# Power.net
KiCad netlist of a schematic drawn in Altium Designer
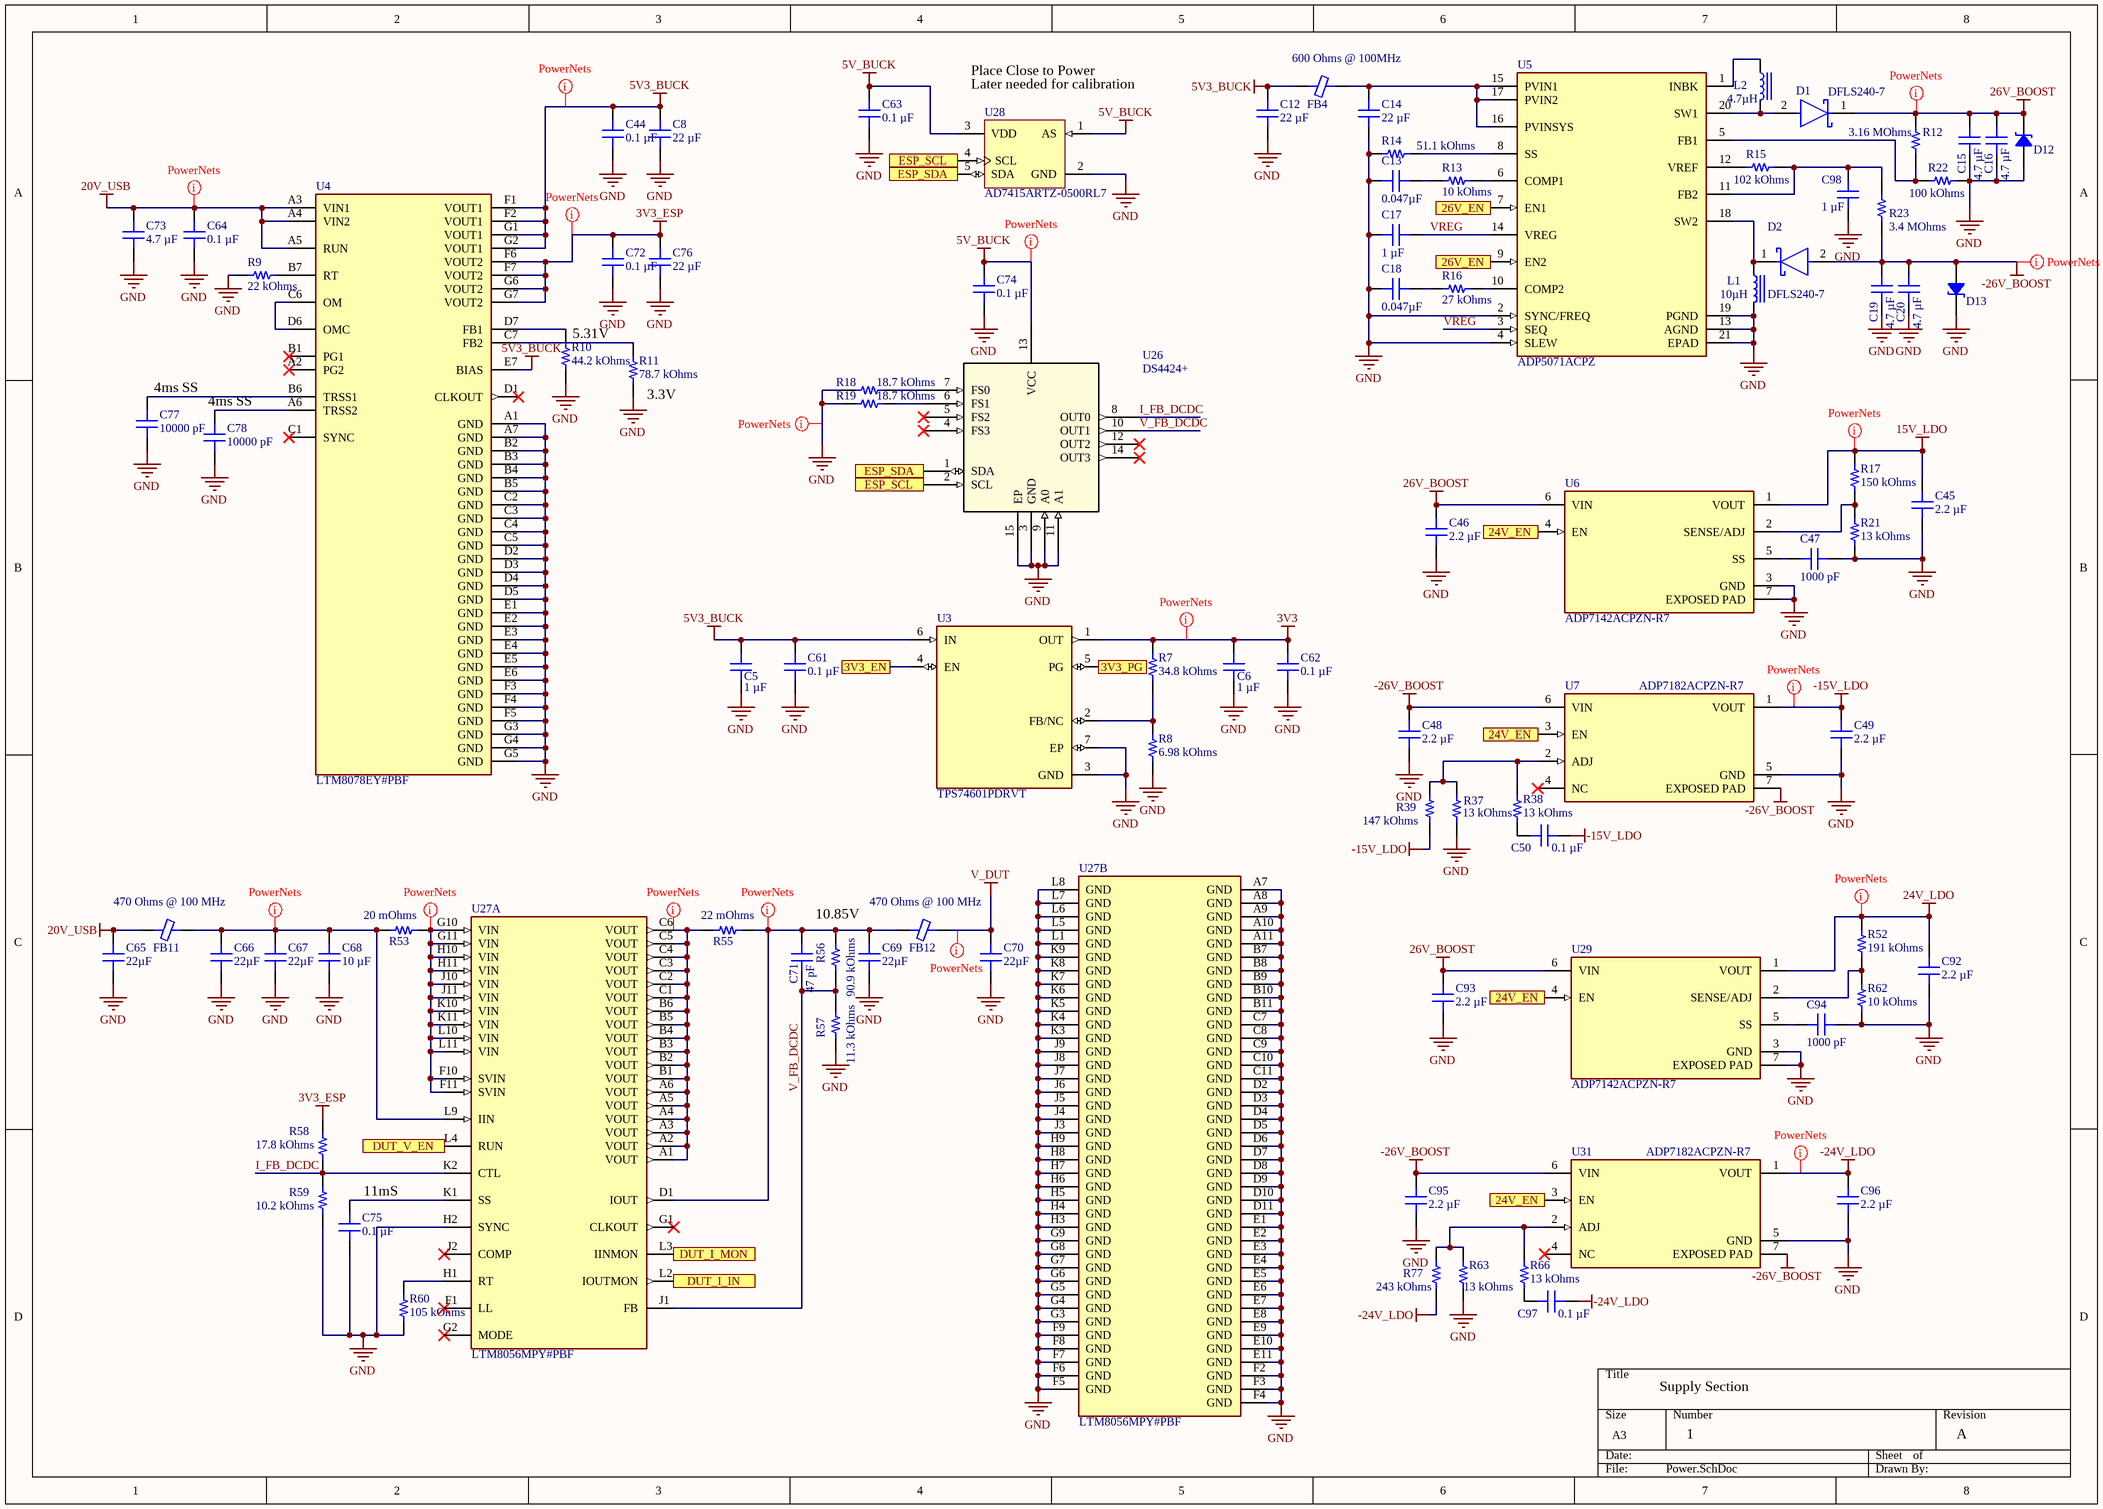
[diagram p0: Power.SchDoc]

(export (version "E")
  (design (tool "Eeschema 10.0.6"))
  (components
    (comp (ref "C5")
      (value "1 µF")
      (footprint "CAP 0603_1608")
      (description "SMT Capacitor")
      (fields
        (field (name "PART NUMBER") "GMC10X7R105M50NT")
        (field (name "MANUFACTURER") "Cal-Chip Electronics, Inc.")
      )
      (libsource (lib "Altium DB") (part "Capacitor"))
    )
    (comp (ref "C6")
      (value "1 µF")
      (footprint "CAP 0603_1608")
      (description "SMT Capacitor")
      (fields
        (field (name "PART NUMBER") "GMC10X7R105M50NT")
        (field (name "MANUFACTURER") "Cal-Chip Electronics, Inc.")
      )
      (libsource (lib "Altium DB") (part "Capacitor"))
    )
    (comp (ref "C8")
      (value "22 µF")
      (footprint "CAP 0603_1608")
      (description "SMT Capacitor")
      (fields
        (field (name "PART NUMBER") "GRM188C61C226ME01D")
        (field (name "MANUFACTURER") "Murata Electronics")
      )
      (libsource (lib "Altium DB") (part "Capacitor"))
    )
    (comp (ref "C12")
      (value "22 µF")
      (footprint "CAP 0603_1608")
      (description "SMT Capacitor")
      (fields
        (field (name "PART NUMBER") "GRM188C61C226ME01D")
        (field (name "MANUFACTURER") "Murata Electronics")
      )
      (libsource (lib "Altium DB") (part "Capacitor"))
    )
    (comp (ref "C13")
      (value "0.047µF")
      (footprint "CAP 0603_1608")
      (description "CAP CER 0.047UF 25V X7R 0603")
      (fields (field (name "MANUFACTURER") "KEMET") (field (name "PART NUMBER") "C0603C473K3RACAUTO"))
      (libsource (lib "") (part "Capacitor_4"))
    )
    (comp (ref "C14")
      (value "22 µF")
      (footprint "CAP 0603_1608")
      (description "SMT Capacitor")
      (fields
        (field (name "PART NUMBER") "GRM188C61C226ME01D")
        (field (name "MANUFACTURER") "Murata Electronics")
      )
      (libsource (lib "Altium DB") (part "Capacitor"))
    )
    (comp (ref "C15")
      (value "4.7 µF")
      (footprint "CAP 0805_2012")
      (description "CAP CER 4.7UF 50V X7R 0805")
      (fields
        (field (name "MANUFACTURER") "TDK Corporation")
        (field (name "PART NUMBER") "CGA4J1X7R1H475K125AC")
      )
      (libsource (lib "") (part "Capacitor_4"))
    )
    (comp (ref "C16")
      (value "4.7 µF")
      (footprint "CAP 0805_2012")
      (description "CAP CER 4.7UF 50V X7R 0805")
      (fields
        (field (name "MANUFACTURER") "TDK Corporation")
        (field (name "PART NUMBER") "CGA4J1X7R1H475K125AC")
      )
      (libsource (lib "") (part "Capacitor_4"))
    )
    (comp (ref "C17")
      (value "1 µF")
      (footprint "CAP 0603_1608")
      (description "SMT Capacitor")
      (fields
        (field (name "PART NUMBER") "GMC10X7R105M50NT")
        (field (name "MANUFACTURER") "Cal-Chip Electronics, Inc.")
      )
      (libsource (lib "Altium DB") (part "Capacitor"))
    )
    (comp (ref "C18")
      (value "0.047µF")
      (footprint "CAP 0603_1608")
      (description "CAP CER 0.047UF 25V X7R 0603")
      (fields (field (name "MANUFACTURER") "KEMET") (field (name "PART NUMBER") "C0603C473K3RACAUTO"))
      (libsource (lib "") (part "Capacitor_4"))
    )
    (comp (ref "C19")
      (value "4.7 µF")
      (footprint "CAP 0805_2012")
      (description "CAP CER 4.7UF 50V X7R 0805")
      (fields
        (field (name "MANUFACTURER") "TDK Corporation")
        (field (name "PART NUMBER") "CGA4J1X7R1H475K125AC")
      )
      (libsource (lib "") (part "Capacitor_4"))
    )
    (comp (ref "C20")
      (value "4.7 µF")
      (footprint "CAP 0805_2012")
      (description "CAP CER 4.7UF 50V X7R 0805")
      (fields
        (field (name "MANUFACTURER") "TDK Corporation")
        (field (name "PART NUMBER") "CGA4J1X7R1H475K125AC")
      )
      (libsource (lib "") (part "Capacitor_4"))
    )
    (comp (ref "C44")
      (value "0.1 µF")
      (footprint "CAP 0603_1608")
      (description "SMT Capacitor")
      (fields (field (name "PART NUMBER") "C0603C104M5RACTU") (field (name "MANUFACTURER") "KEMET"))
      (libsource (lib "Altium DB") (part "Capacitor"))
    )
    (comp (ref "C45")
      (value "2.2 µF")
      (footprint "CAP 0805_2012")
      (description "SMT Capacitor")
      (fields (field (name "PART NUMBER") "UMK212BB7225KG-T") (field (name "MANUFACTURER") "Taiyo Yuden"))
      (libsource (lib "Altium DB") (part "Capacitor"))
    )
    (comp (ref "C46")
      (value "2.2 µF")
      (footprint "CAP 0805_2012")
      (description "SMT Capacitor")
      (fields (field (name "PART NUMBER") "UMK212BB7225KG-T") (field (name "MANUFACTURER") "Taiyo Yuden"))
      (libsource (lib "Altium DB") (part "Capacitor"))
    )
    (comp (ref "C47")
      (value "1000 pF")
      (footprint "CAP 0603_1608")
      (description "CAP CER 1000PF 25V X7R 0603")
      (fields
        (field (name "MANUFACTURER") "Murata Electronics")
        (field (name "PART NUMBER") "GCJ188R71E102KA01D")
      )
      (libsource (lib "") (part "Capacitor_4"))
    )
    (comp (ref "C48")
      (value "2.2 µF")
      (footprint "CAP 0805_2012")
      (description "SMT Capacitor")
      (fields (field (name "PART NUMBER") "UMK212BB7225KG-T") (field (name "MANUFACTURER") "Taiyo Yuden"))
      (libsource (lib "Altium DB") (part "Capacitor"))
    )
    (comp (ref "C49")
      (value "2.2 µF")
      (footprint "CAP 0805_2012")
      (description "SMT Capacitor")
      (fields (field (name "PART NUMBER") "UMK212BB7225KG-T") (field (name "MANUFACTURER") "Taiyo Yuden"))
      (libsource (lib "Altium DB") (part "Capacitor"))
    )
    (comp (ref "C50")
      (value "0.1 µF")
      (footprint "CAP 0603_1608")
      (description "SMT Capacitor")
      (fields (field (name "PART NUMBER") "C0603C104M5RACTU") (field (name "MANUFACTURER") "KEMET"))
      (libsource (lib "Altium DB") (part "Capacitor"))
    )
    (comp (ref "C61")
      (value "0.1 µF")
      (footprint "CAP 0603_1608")
      (description "SMT Capacitor")
      (fields (field (name "PART NUMBER") "C0603C104M5RACTU") (field (name "MANUFACTURER") "KEMET"))
      (libsource (lib "Altium DB") (part "Capacitor"))
    )
    (comp (ref "C62")
      (value "0.1 µF")
      (footprint "CAP 0603_1608")
      (description "SMT Capacitor")
      (fields (field (name "PART NUMBER") "C0603C104M5RACTU") (field (name "MANUFACTURER") "KEMET"))
      (libsource (lib "Altium DB") (part "Capacitor"))
    )
    (comp (ref "C63")
      (value "0.1 µF")
      (footprint "CAP 0603_1608")
      (description "SMT Capacitor")
      (fields (field (name "PART NUMBER") "C0603C104M5RACTU") (field (name "MANUFACTURER") "KEMET"))
      (libsource (lib "Altium DB") (part "Capacitor"))
    )
    (comp (ref "C64")
      (value "0.1 µF")
      (footprint "CAP 0603_1608")
      (description "SMT Capacitor")
      (fields (field (name "PART NUMBER") "C0603C104M5RACTU") (field (name "MANUFACTURER") "KEMET"))
      (libsource (lib "Altium DB") (part "Capacitor"))
    )
    (comp (ref "C65")
      (value "22µF")
      (footprint "CAP 2220_5650 3.0MM")
      (description "CAP 2220 X7R 50V 22UF 20% 2.50MM")
      (fields
        (field (name "MANUFACTURER") "TDK Corporation")
        (field (name "PART NUMBER") "CGA9P3X7R1H226M250KB")
      )
      (libsource (lib "") (part "Capacitor_10"))
    )
    (comp (ref "C66")
      (value "22µF")
      (footprint "CAP 2220_5650 3.0MM")
      (description "CAP 2220 X7R 50V 22UF 20% 2.50MM")
      (fields
        (field (name "MANUFACTURER") "TDK Corporation")
        (field (name "PART NUMBER") "CGA9P3X7R1H226M250KB")
      )
      (libsource (lib "") (part "Capacitor_3"))
    )
    (comp (ref "C67")
      (value "22µF")
      (footprint "CAP 2220_5650 3.0MM")
      (description "CAP 2220 X7R 50V 22UF 20% 2.50MM")
      (fields
        (field (name "MANUFACTURER") "TDK Corporation")
        (field (name "PART NUMBER") "CGA9P3X7R1H226M250KB")
      )
      (libsource (lib "") (part "Capacitor_9"))
    )
    (comp (ref "C68")
      (value "10 µF")
      (footprint "CAP 1210_3225 - 1MM")
      (description "CAP CER 10UF 50V X7R 1210")
      (fields
        (field (name "MANUFACTURER") "Walsin Technology Corporation")
        (field (name "PART NUMBER") "1210B106K500CT")
      )
      (libsource (lib "") (part "Capacitor_5"))
    )
    (comp (ref "C69")
      (value "22µF")
      (footprint "CAP 2220_5650 3.0MM")
      (description "CAP 2220 X7R 50V 22UF 20% 2.50MM")
      (fields
        (field (name "MANUFACTURER") "TDK Corporation")
        (field (name "PART NUMBER") "CGA9P3X7R1H226M250KB")
      )
      (libsource (lib "") (part "Capacitor_2"))
    )
    (comp (ref "C70")
      (value "22µF")
      (footprint "CAP 2220_5650 3.0MM")
      (description "CAP 2220 X7R 50V 22UF 20% 2.50MM")
      (fields
        (field (name "MANUFACTURER") "TDK Corporation")
        (field (name "PART NUMBER") "CGA9P3X7R1H226M250KB")
      )
      (libsource (lib "") (part "Capacitor_6"))
    )
    (comp (ref "C71")
      (value "47 pF")
      (footprint "CAP 0603_1608")
      (description "CAP CER 47PF 50V C0G/NPO 0603")
      (fields (field (name "MANUFACTURER") "Yageo") (field (name "PART NUMBER") "CC0603KRNPO9BN470"))
      (libsource (lib "") (part "Capacitor_8"))
    )
    (comp (ref "C72")
      (value "0.1 µF")
      (footprint "CAP 0603_1608")
      (description "SMT Capacitor")
      (fields (field (name "PART NUMBER") "C0603C104M5RACTU") (field (name "MANUFACTURER") "KEMET"))
      (libsource (lib "Altium DB") (part "Capacitor"))
    )
    (comp (ref "C73")
      (value "4.7 µF")
      (footprint "CAP 0805_2012")
      (description "CAP CER 4.7UF 35V X7R 0805")
      (fields
        (field (name "MANUFACTURER") "Murata Electronics")
        (field (name "PART NUMBER") "GRM21BZ7YA475KE15K")
      )
      (libsource (lib "") (part "Capacitor_1"))
    )
    (comp (ref "C74")
      (value "0.1 µF")
      (footprint "CAP 0603_1608")
      (description "SMT Capacitor")
      (fields (field (name "PART NUMBER") "C0603C104M5RACTU") (field (name "MANUFACTURER") "KEMET"))
      (libsource (lib "Altium DB") (part "Capacitor"))
    )
    (comp (ref "C75")
      (value "0.1 µF")
      (footprint "CAP 0603_1608")
      (description "SMT Capacitor")
      (fields (field (name "PART NUMBER") "C0603C104M5RACTU") (field (name "MANUFACTURER") "KEMET"))
      (libsource (lib "Altium DB") (part "Capacitor"))
    )
    (comp (ref "C76")
      (value "22 µF")
      (footprint "CAP 0603_1608")
      (description "SMT Capacitor")
      (fields
        (field (name "PART NUMBER") "GRM188C61C226ME01D")
        (field (name "MANUFACTURER") "Murata Electronics")
      )
      (libsource (lib "Altium DB") (part "Capacitor"))
    )
    (comp (ref "C77")
      (value "10000 pF")
      (footprint "CAP 0603_1608")
      (description "CAP CER 10000PF 100V X7R 0603")
      (fields (field (name "MANUFACTURER") "Yageo") (field (name "PART NUMBER") "AC0603KRX7R0BB103"))
      (libsource (lib "") (part "Capacitor_7"))
    )
    (comp (ref "C78")
      (value "10000 pF")
      (footprint "CAP 0603_1608")
      (description "CAP CER 10000PF 100V X7R 0603")
      (fields (field (name "MANUFACTURER") "Yageo") (field (name "PART NUMBER") "AC0603KRX7R0BB103"))
      (libsource (lib "") (part "Capacitor_7"))
    )
    (comp (ref "C92")
      (value "2.2 µF")
      (footprint "CAP 0805_2012")
      (description "SMT Capacitor")
      (fields (field (name "PART NUMBER") "UMK212BB7225KG-T") (field (name "MANUFACTURER") "Taiyo Yuden"))
      (libsource (lib "Altium DB") (part "Capacitor"))
    )
    (comp (ref "C93")
      (value "2.2 µF")
      (footprint "CAP 0805_2012")
      (description "SMT Capacitor")
      (fields (field (name "PART NUMBER") "UMK212BB7225KG-T") (field (name "MANUFACTURER") "Taiyo Yuden"))
      (libsource (lib "Altium DB") (part "Capacitor"))
    )
    (comp (ref "C94")
      (value "1000 pF")
      (footprint "CAP 0603_1608")
      (description "CAP CER 1000PF 25V X7R 0603")
      (fields
        (field (name "MANUFACTURER") "Murata Electronics")
        (field (name "PART NUMBER") "GCJ188R71E102KA01D")
      )
      (libsource (lib "") (part "Capacitor_4"))
    )
    (comp (ref "C95")
      (value "2.2 µF")
      (footprint "CAP 0805_2012")
      (description "SMT Capacitor")
      (fields (field (name "PART NUMBER") "UMK212BB7225KG-T") (field (name "MANUFACTURER") "Taiyo Yuden"))
      (libsource (lib "Altium DB") (part "Capacitor"))
    )
    (comp (ref "C96")
      (value "2.2 µF")
      (footprint "CAP 0805_2012")
      (description "SMT Capacitor")
      (fields (field (name "PART NUMBER") "UMK212BB7225KG-T") (field (name "MANUFACTURER") "Taiyo Yuden"))
      (libsource (lib "Altium DB") (part "Capacitor"))
    )
    (comp (ref "C97")
      (value "0.1 µF")
      (footprint "CAP 0603_1608")
      (description "SMT Capacitor")
      (fields (field (name "PART NUMBER") "C0603C104M5RACTU") (field (name "MANUFACTURER") "KEMET"))
      (libsource (lib "Altium DB") (part "Capacitor"))
    )
    (comp (ref "C98")
      (value "1 µF")
      (footprint "CAP 0603_1608")
      (description "SMT Capacitor")
      (fields
        (field (name "PART NUMBER") "GMC10X7R105M50NT")
        (field (name "MANUFACTURER") "Cal-Chip Electronics, Inc.")
      )
      (libsource (lib "Altium DB") (part "Capacitor"))
    )
    (comp (ref "D1")
      (value "DFLS240-7")
      (footprint "FP-PowerDI123-MFG")
      (description "DIODE SCHOTTKY 40V 2A POWERDI123")
      (fields
        (field (name "MANUFACTURER") "Diodes Inc.")
        (field (name "OCTOPART") "https://octopart.com/dfls240-7-diodes+inc.-9289682")
      )
      (libsource (lib "Altium Content Vault") (part "1d6ec82d83fb6aee721767c19dac4b9"))
    )
    (comp (ref "D2")
      (value "DFLS240-7")
      (footprint "FP-PowerDI123-MFG")
      (description "DIODE SCHOTTKY 40V 2A POWERDI123")
      (fields
        (field (name "MANUFACTURER") "Diodes Inc.")
        (field (name "OCTOPART") "https://octopart.com/dfls240-7-diodes+inc.-9289682")
      )
      (libsource (lib "Altium Content Vault") (part "1d6ec82d83fb6aee721767c19dac4b9"))
    )
    (comp (ref "D12")
      (value "BZT52C27-7-F")
      (footprint "SOD-123")
      (description "DIODE ZENER 27V 500MW SOD123")
      (fields (field (name "MANUFACTURER") "Diodes Incorporated") (field (name "TOLERANCE") "±7%"))
      (libsource (lib "Altium DB") (part "Diode Zener"))
    )
    (comp (ref "D13")
      (value "BZT52C27-7-F")
      (footprint "SOD-123")
      (description "DIODE ZENER 27V 500MW SOD123")
      (fields (field (name "MANUFACTURER") "Diodes Incorporated") (field (name "TOLERANCE") "±7%"))
      (libsource (lib "Altium DB") (part "Diode Zener"))
    )
    (comp (ref "FB4")
      (value "600 Ohms @ 100MHz")
      (footprint "FER 0805_2012")
      (description "EMI BEAD FILETER")
      (fields
        (field (name "PART NUMBER") "BBPY00201209601Y00")
        (field (name "MANUFACTURER") "Chilisin Electronics")
      )
      (libsource (lib "Altium DB") (part "Ferrite Chip"))
    )
    (comp (ref "FB11")
      (value "470 Ohms @ 100 MHz")
      (footprint "FER 1206_3216")
      (description "FERRITE BEAD 470 OHM 1206 1LN")
      (fields
        (field (name "PART NUMBER") "BLM31KN471SN1L")
        (field (name "MANUFACTURER") "Murata Electronics")
      )
      (libsource (lib "Altium DB") (part "Ferrite Chip"))
    )
    (comp (ref "FB12")
      (value "470 Ohms @ 100 MHz")
      (footprint "FER 1206_3216")
      (description "FERRITE BEAD 470 OHM 1206 1LN")
      (fields
        (field (name "PART NUMBER") "BLM31KN471SN1L")
        (field (name "MANUFACTURER") "Murata Electronics")
      )
      (libsource (lib "Altium DB") (part "Ferrite Chip"))
    )
    (comp (ref "L1")
      (value "10µH")
      (footprint "IND 1008_2520")
      (description "FIXED IND 10UH 900MA 600 MOHM")
      (fields
        (field (name "PART NUMBER") "DFE252010F-100M=P2")
        (field (name "MANUFACTURER") "Murata Electronics")
      )
      (libsource (lib "Altium DB") (part "Inductor"))
    )
    (comp (ref "L2")
      (value "4.7µH")
      (footprint "IND 1008_2520")
      (description "FIXED IND 4.7UH 1.5A 245MOHM SMD")
      (fields (field (name "PART NUMBER") "LPWI252010S4R7T") (field (name "MANUFACTURER") "Littelfuse Inc."))
      (libsource (lib "Altium DB") (part "Inductor"))
    )
    (comp (ref "R7")
      (value "34.8 kOhms")
      (footprint "RES 0603_1608")
      (description "RES SMD 34.8K OHM 1% 1/10W 0603")
      (fields
        (field (name "PART NUMBER") "ERJ-3EKF3482V")
        (field (name "MANUFACTURER") "Panasonic Electronic Components")
      )
      (libsource (lib "") (part "Resistor_6"))
    )
    (comp (ref "R8")
      (value "6.98 kOhms")
      (footprint "RES 0603_1608")
      (description "RES SMD 6.98K OHM 1% 1/10W 0603")
      (fields
        (field (name "PART NUMBER") "ERJ-3EKF6981V")
        (field (name "MANUFACTURER") "Panasonic Electronic Components")
      )
      (libsource (lib "") (part "Resistor_6"))
    )
    (comp (ref "R9")
      (value "22 kOhms")
      (footprint "RES 0603_1608")
      (description "RES SMD 22K OHM 1% 1/10W 0603")
      (fields
        (field (name "MANUFACTURER") "Panasonic Electronic Components")
        (field (name "PART NUMBER") "ERJ-3EKF2202V")
      )
      (libsource (lib "") (part "Resistor_11"))
    )
    (comp (ref "R10")
      (value "44.2 kOhms")
      (footprint "RES 0603_1608")
      (description "RES SMD 44.2K OHM 1% 1/10W 0603")
      (fields
        (field (name "MANUFACTURER") "Panasonic Electronic Components")
        (field (name "PART NUMBER") "ERJ-3EKF4422V")
      )
      (libsource (lib "") (part "Resistor_4"))
    )
    (comp (ref "R11")
      (value "78.7 kOhms")
      (footprint "RES 0603_1608")
      (description "RES SMD 78.7K OHM 1% 1/10W 0603")
      (fields
        (field (name "MANUFACTURER") "Panasonic Electronic Components")
        (field (name "PART NUMBER") "ERJ-3EKF7872V")
      )
      (libsource (lib "") (part "Resistor_9"))
    )
    (comp (ref "R12")
      (value "3.16 MOhms")
      (footprint "RES 0603_1608")
      (description "RES 3.16M OHM 1% 1/10W 0603")
      (fields
        (field (name "PART NUMBER") "RMCF0603FT3M16")
        (field (name "MANUFACTURER") "Stackpole Electronics Inc")
      )
      (libsource (lib "") (part "Resistor_6"))
    )
    (comp (ref "R13")
      (value "10 kOhms")
      (footprint "RES 0603_1608")
      (description "RES SMD 10K OHM 1% 1/3W 0603")
      (fields
        (field (name "MANUFACTURER") "Panasonic Electronic Components")
        (field (name "PART NUMBER") "ERJ-PA3F1002V")
      )
      (libsource (lib "Altium DB") (part "Resistor"))
    )
    (comp (ref "R14")
      (value "51.1 kOhms")
      (footprint "RES 0603_1608")
      (description "RES SMD 51.1K OHM 1% 1/10W 0603")
      (fields
        (field (name "MANUFACTURER") "Panasonic Electronic Components")
        (field (name "PART NUMBER") "ERJ-3EKF5112V")
      )
      (libsource (lib "Altium DB") (part "Resistor"))
    )
    (comp (ref "R15")
      (value "102 kOhms")
      (footprint "RES 0603_1608")
      (description "RES SMD 102K OHM 1% 1/10W 0603")
      (fields
        (field (name "MANUFACTURER") "Panasonic Electronic Components")
        (field (name "PART NUMBER") "ERJ-3EKF1023V")
      )
      (libsource (lib "Altium DB") (part "Resistor"))
    )
    (comp (ref "R16")
      (value "27 kOhms")
      (footprint "RES 0603_1608")
      (description "RES SMD 27K OHM 1% 1/3W 0603")
      (fields
        (field (name "MANUFACTURER") "Panasonic Electronic Components")
        (field (name "PART NUMBER") "ERJ-PA3F2702V")
      )
      (libsource (lib "Altium DB") (part "Resistor"))
    )
    (comp (ref "R17")
      (value "150 kOhms")
      (footprint "RES 0603_1608")
      (description "RES SMD 150K OHM 1% 1/3W 0603")
      (fields
        (field (name "MANUFACTURER") "Panasonic Electronic Components")
        (field (name "PART NUMBER") "ERJ-PA3F1503V")
      )
      (libsource (lib "") (part "Resistor_14"))
    )
    (comp (ref "R18")
      (value "18.7 kOhms")
      (footprint "RES 0603_1608")
      (description "RES SMD 18.7K OHM 1% 1/10W 0603")
      (fields
        (field (name "MANUFACTURER") "Panasonic Electronic Components")
        (field (name "PART NUMBER") "ERJ-3EKF1872V")
      )
      (libsource (lib "") (part "Resistor_5"))
    )
    (comp (ref "R19")
      (value "18.7 kOhms")
      (footprint "RES 0603_1608")
      (description "RES SMD 18.7K OHM 1% 1/10W 0603")
      (fields
        (field (name "MANUFACTURER") "Panasonic Electronic Components")
        (field (name "PART NUMBER") "ERJ-3EKF1872V")
      )
      (libsource (lib "") (part "Resistor_5"))
    )
    (comp (ref "R21")
      (value "13 kOhms")
      (footprint "RES 0603_1608")
      (description "RES SMD 13K OHM 1% 1/3W 0603")
      (fields
        (field (name "MANUFACTURER") "Panasonic Electronic Components")
        (field (name "PART NUMBER") "ERJ-PA3F1302V")
      )
      (libsource (lib "") (part "Resistor_3"))
    )
    (comp (ref "R22")
      (value "100 kOhms")
      (footprint "RES 0603_1608")
      (description "RES SMD 100K OHM 1% 1/3W 0603")
      (fields
        (field (name "MANUFACTURER") "Panasonic Electronic Components")
        (field (name "PART NUMBER") "ERJ-PA3F1003V")
      )
      (libsource (lib "Altium DB") (part "Resistor"))
    )
    (comp (ref "R23")
      (value "3.4 MOhms")
      (footprint "RES 0603_1608")
      (description "RES 3.4M OHM 1% 1/10W 0603")
      (fields
        (field (name "MANUFACTURER") "Stackpole Electronics Inc")
        (field (name "PART NUMBER") "RMCF0603FT3M40")
      )
      (libsource (lib "Altium DB") (part "Resistor"))
    )
    (comp (ref "R37")
      (value "13 kOhms")
      (footprint "RES 0603_1608")
      (description "RES SMD 13K OHM 1% 1/3W 0603")
      (fields
        (field (name "MANUFACTURER") "Panasonic Electronic Components")
        (field (name "PART NUMBER") "ERJ-PA3F1302V")
      )
      (libsource (lib "") (part "Resistor_10"))
    )
    (comp (ref "R38")
      (value "13 kOhms")
      (footprint "RES 0603_1608")
      (description "RES SMD 13K OHM 1% 1/3W 0603")
      (fields
        (field (name "MANUFACTURER") "Panasonic Electronic Components")
        (field (name "PART NUMBER") "ERJ-PA3F1302V")
      )
      (libsource (lib "Altium DB") (part "Resistor"))
    )
    (comp (ref "R39")
      (value "147 kOhms")
      (footprint "RES 0603_1608")
      (description "RES SMD 147K OHM 1% 1/10W 0603")
      (fields
        (field (name "MANUFACTURER") "Panasonic Electronic Components")
        (field (name "PART NUMBER") "ERJ-3EKF1473V")
      )
      (libsource (lib "") (part "Resistor_1"))
    )
    (comp (ref "R52")
      (value "191 kOhms")
      (footprint "RES 0603_1608")
      (description "RES SMD 191K OHM 1% 1/10W 0603")
      (fields
        (field (name "MANUFACTURER") "Panasonic Electronic Components")
        (field (name "PART NUMBER") "ERJ-3EKF1913V")
      )
      (libsource (lib "Altium DB") (part "Resistor"))
    )
    (comp (ref "R53")
      (value "20 mOhms")
      (footprint "STACKPOLE CSR1206")
      (description "RES 0.02 OHM 1% 1W 1206")
      (fields
        (field (name "PART NUMBER") "ERJ-8BWFR020V")
        (field (name "MANUFACTURER") "Panasonic Electronic Components")
      )
      (libsource (lib "") (part "Resistor_6"))
    )
    (comp (ref "R55")
      (value "22 mOhms")
      (footprint "STACKPOLE CSR1206")
      (description "RES 0.022 OHM 1W 1206 WIDE")
      (fields
        (field (name "PART NUMBER") "ERJ-D2DFR022V")
        (field (name "MANUFACTURER") "Panasonic Electronic Components")
      )
      (libsource (lib "") (part "Resistor_6"))
    )
    (comp (ref "R56")
      (value "90.9 kOhms")
      (footprint "RES 0603_1608")
      (description "RES SMD 90.9K OHM 1% 1/10W 0603")
      (fields
        (field (name "MANUFACTURER") "Panasonic Electronic Components")
        (field (name "PART NUMBER") "ERJ-3EKF9092V")
      )
      (libsource (lib "") (part "Resistor_13"))
    )
    (comp (ref "R57")
      (value "11.3 kOhms")
      (footprint "RES 0603_1608")
      (description "RES SMD 11.3K OHM 1% 1/10W 0603")
      (fields
        (field (name "MANUFACTURER") "Panasonic Electronic Components")
        (field (name "PART NUMBER") "ERJ-3EKF1132V")
      )
      (libsource (lib "") (part "Resistor_7"))
    )
    (comp (ref "R58")
      (value "17.8 kOhms")
      (footprint "RES 0603_1608")
      (description "RES SMD 17.8K OHM 1% 1/10W 0603")
      (fields
        (field (name "MANUFACTURER") "Panasonic Electronic Components")
        (field (name "PART NUMBER") "ERJ-3EKF1782V")
      )
      (libsource (lib "") (part "Resistor_2"))
    )
    (comp (ref "R59")
      (value "10.2 kOhms")
      (footprint "RES 0603_1608")
      (description "RES SMD 10.2K OHM 1% 1/10W 0603")
      (fields
        (field (name "MANUFACTURER") "Panasonic Electronic Components")
        (field (name "PART NUMBER") "ERJ-3EKF1022V")
      )
      (libsource (lib "") (part "Resistor_8"))
    )
    (comp (ref "R60")
      (value "105 kOhms")
      (footprint "RES 0603_1608")
      (description "RES SMD 105K OHM 1% 1/10W 0603")
      (fields
        (field (name "MANUFACTURER") "Panasonic Electronic Components")
        (field (name "PART NUMBER") "ERJ-3EKF1053V")
      )
      (libsource (lib "") (part "Resistor_12"))
    )
    (comp (ref "R62")
      (value "10 kOhms")
      (footprint "RES 0603_1608")
      (description "RES SMD 10K OHM 1% 1/3W 0603")
      (fields
        (field (name "MANUFACTURER") "Panasonic Electronic Components")
        (field (name "PART NUMBER") "ERJ-PA3F1002V")
      )
      (libsource (lib "Altium DB") (part "Resistor"))
    )
    (comp (ref "R63")
      (value "13 kOhms")
      (footprint "RES 0603_1608")
      (description "RES SMD 13K OHM 1% 1/3W 0603")
      (fields
        (field (name "MANUFACTURER") "Panasonic Electronic Components")
        (field (name "PART NUMBER") "ERJ-PA3F1302V")
      )
      (libsource (lib "Altium DB") (part "Resistor"))
    )
    (comp (ref "R66")
      (value "13 kOhms")
      (footprint "RES 0603_1608")
      (description "RES SMD 13K OHM 1% 1/3W 0603")
      (fields
        (field (name "MANUFACTURER") "Panasonic Electronic Components")
        (field (name "PART NUMBER") "ERJ-PA3F1302V")
      )
      (libsource (lib "Altium DB") (part "Resistor"))
    )
    (comp (ref "R77")
      (value "243 kOhms")
      (footprint "RES 0603_1608")
      (description "RES SMD 243K OHM 1% 1/10W 0603")
      (fields
        (field (name "MANUFACTURER") "Panasonic Electronic Components")
        (field (name "PART NUMBER") "ERJ-3EKF2433V")
      )
      (libsource (lib "Altium DB") (part "Resistor"))
    )
    (comp (ref "U3")
      (value "TPS74601PDRVT")
      (footprint "SON65P200X200X80-7N")
      (fields (field (name "MF") "Texas Instruments"))
      (libsource (lib "Lib") (part "TPS74601PDRVT"))
    )
    (comp (ref "U4")
      (value "LTM8078EY#PBF")
      (footprint "FP-BGA-49-05-08-1518-IPC_C")
      (description "DUAL 40VIN, 3A SILENT SWITCR UMO")
      (libsource (lib "Altium Content Vault") (part "4060324c9a51752e3d8da8510a218c1"))
    )
    (comp (ref "U5")
      (value "ADP5071ACPZ")
      (footprint "FP-CP-20-8-IPC_A")
      (description "IC REG BST SEPIC ADJ DL 20LFCSP")
      (libsource (lib "Altium Content Vault") (part "a0da9f0c9ee1d2c76b9f5812812a2d0"))
    )
    (comp (ref "U6")
      (value "ADP7142ACPZN-R7")
      (footprint "FP-CP-6-3-IPC_B")
      (description "IC REG LIN POS ADJ 200MA 6LFCSP")
      (libsource (lib "Altium Content Vault") (part "c24023da3caa9f5dbb5c8b2503cd30e"))
    )
    (comp (ref "U7")
      (value "ADP7182ACPZN-R7")
      (footprint "FP-CP-6-3-IPC_B")
      (description "IC REG LIN NEG ADJ 200MA 6LFCSP")
      (libsource (lib "Altium Content Vault") (part "26cf1b2ac9ff142030e38a544d8691f"))
    )
    (comp (ref "U26")
      (value "DS4424+")
      (footprint "21-0137_T1433+2_MXM")
      (description "Two-/Four-Channel, IÂ²C, 7-Bit Sink/Source Current DAC")
      (fields
        (field (name "MANUFACTURER_PART_NUMBER") "ds4424n+")
        (field (name "COPYRIGHT") "Copyright (C) 2026 Ultra Librarian. All rights reserved.")
      )
      (libsource (lib "Lib") (part "DS4424"))
    )
    (comp (ref "U27")
      (value "LTM8056MPY#PBF")
      (footprint "FP-BGA-121-05-08-1891-IPC_C")
      (description "DC DC CONVERTER 1.2-48V")
      (libsource (lib "Lib") (part "LTM8056MPY#PBF"))
    )
    (comp (ref "U28")
      (value "AD7415ARTZ-0500RL7")
      (footprint "ADI-RJ-5_M")
      (fields (field (name "MANUFACTURER") "Analog Devices"))
      (libsource (lib "Lib") (part "AD7415ARTZ-0500RL7"))
    )
    (comp (ref "U29")
      (value "ADP7142ACPZN-R7")
      (footprint "FP-CP-6-3-IPC_B")
      (description "IC REG LIN POS ADJ 200MA 6LFCSP")
      (libsource (lib "Altium Content Vault") (part "c24023da3caa9f5dbb5c8b2503cd30e"))
    )
    (comp (ref "U31")
      (value "ADP7182ACPZN-R7")
      (footprint "FP-CP-6-3-IPC_B")
      (description "IC REG LIN NEG ADJ 200MA 6LFCSP")
      (libsource (lib "Altium Content Vault") (part "26cf1b2ac9ff142030e38a544d8691f"))
    )
  )
  (nets
    (net (code "1") (name "-15V_LDO") (class "Default")
      (node (ref "C49") (pin "2") (pinfunction "2_2") (pintype "passive"))
      (node (ref "C50") (pin "1") (pinfunction "1_1") (pintype "passive"))
      (node (ref "R39") (pin "1") (pinfunction "1_1") (pintype "passive"))
      (node (ref "U7") (pin "1") (pinfunction "VOUT_1") (pintype "power_in"))
    )
    (net (code "2") (name "-24V_LDO") (class "Default")
      (node (ref "C96") (pin "2") (pinfunction "2_2") (pintype "passive"))
      (node (ref "C97") (pin "1") (pinfunction "1_1") (pintype "passive"))
      (node (ref "R77") (pin "1") (pinfunction "1_1") (pintype "passive"))
      (node (ref "U31") (pin "1") (pinfunction "VOUT_1") (pintype "power_in"))
    )
    (net (code "3") (name "-26V_BOOST") (class "Default")
      (node (ref "C19") (pin "2") (pinfunction "2_2") (pintype "passive"))
      (node (ref "C20") (pin "2") (pinfunction "2_2") (pintype "passive"))
      (node (ref "C48") (pin "2") (pinfunction "2_2") (pintype "passive"))
      (node (ref "C95") (pin "2") (pinfunction "2_2") (pintype "passive"))
      (node (ref "D13") (pin "1") (pinfunction "1_1") (pintype "passive"))
      (node (ref "D2") (pin "2") (pinfunction "A_2") (pintype "passive"))
      (node (ref "R23") (pin "1") (pinfunction "1_1") (pintype "passive"))
      (node (ref "U31") (pin "6") (pinfunction "VIN_6") (pintype "power_in"))
      (node (ref "U31") (pin "7") (pinfunction "EXPOSED_PAD_7") (pintype "power_in"))
      (node (ref "U7") (pin "6") (pinfunction "VIN_6") (pintype "power_in"))
      (node (ref "U7") (pin "7") (pinfunction "EXPOSED_PAD_7") (pintype "power_in"))
    )
    (net (code "4") (name "/3V3_EN") (class "Default")
      (node (ref "U3") (pin "4") (pinfunction "EN_4") (pintype "bidirectional"))
    )
    (net (code "5") (name "/3V3_PG") (class "Default")
      (node (ref "U3") (pin "5") (pinfunction "PG_5") (pintype "bidirectional"))
    )
    (net (code "6") (name "/24V_EN") (class "Default")
      (node (ref "U29") (pin "4") (pinfunction "EN_4") (pintype "input"))
      (node (ref "U31") (pin "3") (pinfunction "EN_3") (pintype "input"))
      (node (ref "U6") (pin "4") (pinfunction "EN_4") (pintype "input"))
      (node (ref "U7") (pin "3") (pinfunction "EN_3") (pintype "input"))
    )
    (net (code "7") (name "/26V_EN") (class "Default")
      (node (ref "U5") (pin "7") (pinfunction "EN1_7") (pintype "input"))
      (node (ref "U5") (pin "9") (pinfunction "EN2_9") (pintype "input"))
    )
    (net (code "8") (name "/DUT_I_IN") (class "Default")
      (node (ref "U27") (pin "L2") (pinfunction "IOUTMON_L2") (pintype "output"))
    )
    (net (code "9") (name "/DUT_I_MON") (class "Default")
      (node (ref "U27") (pin "L3") (pinfunction "IINMON_L3") (pintype "passive"))
    )
    (net (code "10") (name "/DUT_V_EN") (class "Default")
      (node (ref "U27") (pin "L4") (pinfunction "RUN_L4") (pintype "passive"))
    )
    (net (code "11") (name "/ESP_SCL") (class "Default")
      (node (ref "U26") (pin "2") (pinfunction "SCL_2") (pintype "input"))
      (node (ref "U28") (pin "4") (pinfunction "SCL_4") (pintype "input"))
    )
    (net (code "12") (name "/ESP_SDA") (class "Default")
      (node (ref "U26") (pin "1") (pinfunction "SDA_1") (pintype "bidirectional"))
      (node (ref "U28") (pin "5") (pinfunction "SDA_5") (pintype "bidirectional"))
    )
    (net (code "13") (name "/I_FB_DCDC") (class "Default")
      (node (ref "R58") (pin "1") (pinfunction "1_1") (pintype "passive"))
      (node (ref "R59") (pin "2") (pinfunction "2_2") (pintype "passive"))
      (node (ref "U26") (pin "8") (pinfunction "OUT0_8") (pintype "output"))
      (node (ref "U27") (pin "K2") (pinfunction "CTL_K2") (pintype "passive"))
    )
    (net (code "14") (name "/VREG") (class "Default")
      (node (ref "C17") (pin "1") (pinfunction "1_1") (pintype "passive"))
      (node (ref "U5") (pin "14") (pinfunction "VREG_14") (pintype "passive"))
      (node (ref "U5") (pin "3") (pinfunction "SEQ_3") (pintype "input"))
    )
    (net (code "15") (name "/V_FB_DCDC") (class "Default")
      (node (ref "C71") (pin "1") (pinfunction "1_1") (pintype "passive"))
      (node (ref "R56") (pin "1") (pinfunction "1_1") (pintype "passive"))
      (node (ref "R57") (pin "2") (pinfunction "2_2") (pintype "passive"))
      (node (ref "U26") (pin "10") (pinfunction "OUT1_10") (pintype "output"))
      (node (ref "U27") (pin "J1") (pinfunction "FB_J1") (pintype "passive"))
    )
    (net (code "16") (name "3V3") (class "Default")
      (node (ref "C6") (pin "2") (pinfunction "2_2") (pintype "passive"))
      (node (ref "C62") (pin "2") (pinfunction "2_2") (pintype "passive"))
      (node (ref "R7") (pin "2") (pinfunction "2_2") (pintype "passive"))
      (node (ref "U3") (pin "1") (pinfunction "OUT_1") (pintype "output"))
    )
    (net (code "17") (name "3V3_ESP") (class "Default")
      (node (ref "C72") (pin "2") (pinfunction "2_2") (pintype "passive"))
      (node (ref "C76") (pin "2") (pinfunction "2_2") (pintype "passive"))
      (node (ref "R58") (pin "2") (pinfunction "2_2") (pintype "passive"))
      (node (ref "U4") (pin "F6") (pinfunction "VOUT2_F6") (pintype "power_in"))
      (node (ref "U4") (pin "F7") (pinfunction "VOUT2_F7") (pintype "power_in"))
      (node (ref "U4") (pin "G6") (pinfunction "VOUT2_G6") (pintype "power_in"))
      (node (ref "U4") (pin "G7") (pinfunction "VOUT2_G7") (pintype "power_in"))
    )
    (net (code "18") (name "5V3_BUCK") (class "Default")
      (node (ref "C12") (pin "2") (pinfunction "2_2") (pintype "passive"))
      (node (ref "C44") (pin "2") (pinfunction "2_2") (pintype "passive"))
      (node (ref "C5") (pin "2") (pinfunction "2_2") (pintype "passive"))
      (node (ref "C61") (pin "2") (pinfunction "2_2") (pintype "passive"))
      (node (ref "C8") (pin "2") (pinfunction "2_2") (pintype "passive"))
      (node (ref "FB4") (pin "1") (pinfunction "1_1") (pintype "passive"))
      (node (ref "U3") (pin "6") (pinfunction "IN_6") (pintype "input"))
      (node (ref "U4") (pin "E7") (pinfunction "BIAS_E7") (pintype "passive"))
      (node (ref "U4") (pin "F1") (pinfunction "VOUT1_F1") (pintype "power_in"))
      (node (ref "U4") (pin "F2") (pinfunction "VOUT1_F2") (pintype "power_in"))
      (node (ref "U4") (pin "G1") (pinfunction "VOUT1_G1") (pintype "power_in"))
      (node (ref "U4") (pin "G2") (pinfunction "VOUT1_G2") (pintype "power_in"))
    )
    (net (code "19") (name "5V_BUCK") (class "Default")
      (node (ref "C63") (pin "2") (pinfunction "2_2") (pintype "passive"))
      (node (ref "C74") (pin "2") (pinfunction "2_2") (pintype "passive"))
      (node (ref "U26") (pin "13") (pinfunction "VCC_13") (pintype "power_in"))
      (node (ref "U28") (pin "1") (pinfunction "AS_1") (pintype "input"))
      (node (ref "U28") (pin "3") (pinfunction "VDD_3") (pintype "power_in"))
    )
    (net (code "20") (name "15V_LDO") (class "Default")
      (node (ref "C45") (pin "2") (pinfunction "2_2") (pintype "passive"))
      (node (ref "R17") (pin "2") (pinfunction "2_2") (pintype "passive"))
      (node (ref "U6") (pin "1") (pinfunction "VOUT_1") (pintype "power_in"))
    )
    (net (code "21") (name "20V_USB") (class "Default")
      (node (ref "C64") (pin "2") (pinfunction "2_2") (pintype "passive"))
      (node (ref "C65") (pin "2") (pinfunction "2_2") (pintype "passive"))
      (node (ref "C73") (pin "2") (pinfunction "2_2") (pintype "passive"))
      (node (ref "FB11") (pin "1") (pinfunction "1_1") (pintype "passive"))
      (node (ref "U4") (pin "A3") (pinfunction "VIN1_A3") (pintype "power_in"))
      (node (ref "U4") (pin "A4") (pinfunction "VIN2_A4") (pintype "power_in"))
      (node (ref "U4") (pin "A5") (pinfunction "RUN_A5") (pintype "passive"))
    )
    (net (code "22") (name "24V_LDO") (class "Default")
      (node (ref "C92") (pin "2") (pinfunction "2_2") (pintype "passive"))
      (node (ref "R52") (pin "1") (pinfunction "1_1") (pintype "passive"))
      (node (ref "U29") (pin "1") (pinfunction "VOUT_1") (pintype "power_in"))
    )
    (net (code "23") (name "26V_BOOST") (class "Default")
      (node (ref "C15") (pin "2") (pinfunction "2_2") (pintype "passive"))
      (node (ref "C16") (pin "2") (pinfunction "2_2") (pintype "passive"))
      (node (ref "C46") (pin "2") (pinfunction "2_2") (pintype "passive"))
      (node (ref "C93") (pin "2") (pinfunction "2_2") (pintype "passive"))
      (node (ref "D1") (pin "1") (pinfunction "C_1") (pintype "passive"))
      (node (ref "D12") (pin "2") (pinfunction "2_2") (pintype "passive"))
      (node (ref "R12") (pin "1") (pinfunction "1_1") (pintype "passive"))
      (node (ref "U29") (pin "6") (pinfunction "VIN_6") (pintype "power_in"))
      (node (ref "U6") (pin "6") (pinfunction "VIN_6") (pintype "power_in"))
    )
    (net (code "24") (name "GND") (class "Default")
      (node (ref "C12") (pin "1") (pinfunction "1_1") (pintype "passive"))
      (node (ref "C13") (pin "1") (pinfunction "1_1") (pintype "passive"))
      (node (ref "C14") (pin "1") (pinfunction "1_1") (pintype "passive"))
      (node (ref "C15") (pin "1") (pinfunction "1_1") (pintype "passive"))
      (node (ref "C16") (pin "1") (pinfunction "1_1") (pintype "passive"))
      (node (ref "C17") (pin "2") (pinfunction "2_2") (pintype "passive"))
      (node (ref "C18") (pin "1") (pinfunction "1_1") (pintype "passive"))
      (node (ref "C19") (pin "1") (pinfunction "1_1") (pintype "passive"))
      (node (ref "C20") (pin "1") (pinfunction "1_1") (pintype "passive"))
      (node (ref "C44") (pin "1") (pinfunction "1_1") (pintype "passive"))
      (node (ref "C45") (pin "1") (pinfunction "1_1") (pintype "passive"))
      (node (ref "C46") (pin "1") (pinfunction "1_1") (pintype "passive"))
      (node (ref "C47") (pin "2") (pinfunction "2_2") (pintype "passive"))
      (node (ref "C48") (pin "1") (pinfunction "1_1") (pintype "passive"))
      (node (ref "C49") (pin "1") (pinfunction "1_1") (pintype "passive"))
      (node (ref "C5") (pin "1") (pinfunction "1_1") (pintype "passive"))
      (node (ref "C6") (pin "1") (pinfunction "1_1") (pintype "passive"))
      (node (ref "C61") (pin "1") (pinfunction "1_1") (pintype "passive"))
      (node (ref "C62") (pin "1") (pinfunction "1_1") (pintype "passive"))
      (node (ref "C63") (pin "1") (pinfunction "1_1") (pintype "passive"))
      (node (ref "C64") (pin "1") (pinfunction "1_1") (pintype "passive"))
      (node (ref "C65") (pin "1") (pinfunction "1_1") (pintype "passive"))
      (node (ref "C66") (pin "1") (pinfunction "1_1") (pintype "passive"))
      (node (ref "C67") (pin "1") (pinfunction "1_1") (pintype "passive"))
      (node (ref "C68") (pin "1") (pinfunction "1_1") (pintype "passive"))
      (node (ref "C69") (pin "1") (pinfunction "1_1") (pintype "passive"))
      (node (ref "C70") (pin "1") (pinfunction "1_1") (pintype "passive"))
      (node (ref "C72") (pin "1") (pinfunction "1_1") (pintype "passive"))
      (node (ref "C73") (pin "1") (pinfunction "1_1") (pintype "passive"))
      (node (ref "C74") (pin "1") (pinfunction "1_1") (pintype "passive"))
      (node (ref "C75") (pin "1") (pinfunction "1_1") (pintype "passive"))
      (node (ref "C76") (pin "1") (pinfunction "1_1") (pintype "passive"))
      (node (ref "C77") (pin "1") (pinfunction "1_1") (pintype "passive"))
      (node (ref "C78") (pin "1") (pinfunction "1_1") (pintype "passive"))
      (node (ref "C8") (pin "1") (pinfunction "1_1") (pintype "passive"))
      (node (ref "C92") (pin "1") (pinfunction "1_1") (pintype "passive"))
      (node (ref "C93") (pin "1") (pinfunction "1_1") (pintype "passive"))
      (node (ref "C94") (pin "2") (pinfunction "2_2") (pintype "passive"))
      (node (ref "C95") (pin "1") (pinfunction "1_1") (pintype "passive"))
      (node (ref "C96") (pin "1") (pinfunction "1_1") (pintype "passive"))
      (node (ref "C98") (pin "1") (pinfunction "1_1") (pintype "passive"))
      (node (ref "D12") (pin "1") (pinfunction "1_1") (pintype "passive"))
      (node (ref "D13") (pin "2") (pinfunction "2_2") (pintype "passive"))
      (node (ref "L1") (pin "2") (pinfunction "2_2") (pintype "passive"))
      (node (ref "R10") (pin "1") (pinfunction "1_1") (pintype "passive"))
      (node (ref "R11") (pin "1") (pinfunction "1_1") (pintype "passive"))
      (node (ref "R14") (pin "1") (pinfunction "1_1") (pintype "passive"))
      (node (ref "R18") (pin "1") (pinfunction "1_1") (pintype "passive"))
      (node (ref "R19") (pin "1") (pinfunction "1_1") (pintype "passive"))
      (node (ref "R21") (pin "1") (pinfunction "1_1") (pintype "passive"))
      (node (ref "R22") (pin "1") (pinfunction "1_1") (pintype "passive"))
      (node (ref "R37") (pin "1") (pinfunction "1_1") (pintype "passive"))
      (node (ref "R57") (pin "1") (pinfunction "1_1") (pintype "passive"))
      (node (ref "R59") (pin "1") (pinfunction "1_1") (pintype "passive"))
      (node (ref "R60") (pin "1") (pinfunction "1_1") (pintype "passive"))
      (node (ref "R62") (pin "1") (pinfunction "1_1") (pintype "passive"))
      (node (ref "R63") (pin "1") (pinfunction "1_1") (pintype "passive"))
      (node (ref "R8") (pin "1") (pinfunction "1_1") (pintype "passive"))
      (node (ref "R9") (pin "1") (pinfunction "1_1") (pintype "passive"))
      (node (ref "U26") (pin "11") (pinfunction "A1_11") (pintype "input"))
      (node (ref "U26") (pin "15") (pinfunction "EP_15") (pintype "passive"))
      (node (ref "U26") (pin "3") (pinfunction "GND_3") (pintype "power_in"))
      (node (ref "U26") (pin "9") (pinfunction "A0_9") (pintype "input"))
      (node (ref "U27") (pin "A10") (pinfunction "GND_A10") (pintype "power_in"))
      (node (ref "U27") (pin "A11") (pinfunction "GND_A11") (pintype "power_in"))
      (node (ref "U27") (pin "A7") (pinfunction "GND_A7") (pintype "power_in"))
      (node (ref "U27") (pin "A8") (pinfunction "GND_A8") (pintype "power_in"))
      (node (ref "U27") (pin "A9") (pinfunction "GND_A9") (pintype "power_in"))
      (node (ref "U27") (pin "B10") (pinfunction "GND_B10") (pintype "power_in"))
      (node (ref "U27") (pin "B11") (pinfunction "GND_B11") (pintype "power_in"))
      (node (ref "U27") (pin "B7") (pinfunction "GND_B7") (pintype "power_in"))
      (node (ref "U27") (pin "B8") (pinfunction "GND_B8") (pintype "power_in"))
      (node (ref "U27") (pin "B9") (pinfunction "GND_B9") (pintype "power_in"))
      (node (ref "U27") (pin "C10") (pinfunction "GND_C10") (pintype "power_in"))
      (node (ref "U27") (pin "C11") (pinfunction "GND_C11") (pintype "power_in"))
      (node (ref "U27") (pin "C7") (pinfunction "GND_C7") (pintype "power_in"))
      (node (ref "U27") (pin "C8") (pinfunction "GND_C8") (pintype "power_in"))
      (node (ref "U27") (pin "C9") (pinfunction "GND_C9") (pintype "power_in"))
      (node (ref "U27") (pin "D10") (pinfunction "GND_D10") (pintype "power_in"))
      (node (ref "U27") (pin "D11") (pinfunction "GND_D11") (pintype "power_in"))
      (node (ref "U27") (pin "D2") (pinfunction "GND_D2") (pintype "power_in"))
      (node (ref "U27") (pin "D3") (pinfunction "GND_D3") (pintype "power_in"))
      (node (ref "U27") (pin "D4") (pinfunction "GND_D4") (pintype "power_in"))
      (node (ref "U27") (pin "D5") (pinfunction "GND_D5") (pintype "power_in"))
      (node (ref "U27") (pin "D6") (pinfunction "GND_D6") (pintype "power_in"))
      (node (ref "U27") (pin "D7") (pinfunction "GND_D7") (pintype "power_in"))
      (node (ref "U27") (pin "D8") (pinfunction "GND_D8") (pintype "power_in"))
      (node (ref "U27") (pin "D9") (pinfunction "GND_D9") (pintype "power_in"))
      (node (ref "U27") (pin "E1") (pinfunction "GND_E1") (pintype "power_in"))
      (node (ref "U27") (pin "E10") (pinfunction "GND_E10") (pintype "power_in"))
      (node (ref "U27") (pin "E11") (pinfunction "GND_E11") (pintype "power_in"))
      (node (ref "U27") (pin "E2") (pinfunction "GND_E2") (pintype "power_in"))
      (node (ref "U27") (pin "E3") (pinfunction "GND_E3") (pintype "power_in"))
      (node (ref "U27") (pin "E4") (pinfunction "GND_E4") (pintype "power_in"))
      (node (ref "U27") (pin "E5") (pinfunction "GND_E5") (pintype "power_in"))
      (node (ref "U27") (pin "E6") (pinfunction "GND_E6") (pintype "power_in"))
      (node (ref "U27") (pin "E7") (pinfunction "GND_E7") (pintype "power_in"))
      (node (ref "U27") (pin "E8") (pinfunction "GND_E8") (pintype "power_in"))
      (node (ref "U27") (pin "E9") (pinfunction "GND_E9") (pintype "power_in"))
      (node (ref "U27") (pin "F2") (pinfunction "GND_F2") (pintype "power_in"))
      (node (ref "U27") (pin "F3") (pinfunction "GND_F3") (pintype "power_in"))
      (node (ref "U27") (pin "F4") (pinfunction "GND_F4") (pintype "power_in"))
      (node (ref "U27") (pin "F5") (pinfunction "GND_F5") (pintype "power_in"))
      (node (ref "U27") (pin "F6") (pinfunction "GND_F6") (pintype "power_in"))
      (node (ref "U27") (pin "F7") (pinfunction "GND_F7") (pintype "power_in"))
      (node (ref "U27") (pin "F8") (pinfunction "GND_F8") (pintype "power_in"))
      (node (ref "U27") (pin "F9") (pinfunction "GND_F9") (pintype "power_in"))
      (node (ref "U27") (pin "G3") (pinfunction "GND_G3") (pintype "power_in"))
      (node (ref "U27") (pin "G4") (pinfunction "GND_G4") (pintype "power_in"))
      (node (ref "U27") (pin "G5") (pinfunction "GND_G5") (pintype "power_in"))
      (node (ref "U27") (pin "G6") (pinfunction "GND_G6") (pintype "power_in"))
      (node (ref "U27") (pin "G7") (pinfunction "GND_G7") (pintype "power_in"))
      (node (ref "U27") (pin "G8") (pinfunction "GND_G8") (pintype "power_in"))
      (node (ref "U27") (pin "G9") (pinfunction "GND_G9") (pintype "power_in"))
      (node (ref "U27") (pin "H2") (pinfunction "SYNC_H2") (pintype "passive"))
      (node (ref "U27") (pin "H3") (pinfunction "GND_H3") (pintype "power_in"))
      (node (ref "U27") (pin "H4") (pinfunction "GND_H4") (pintype "power_in"))
      (node (ref "U27") (pin "H5") (pinfunction "GND_H5") (pintype "power_in"))
      (node (ref "U27") (pin "H6") (pinfunction "GND_H6") (pintype "power_in"))
      (node (ref "U27") (pin "H7") (pinfunction "GND_H7") (pintype "power_in"))
      (node (ref "U27") (pin "H8") (pinfunction "GND_H8") (pintype "power_in"))
      (node (ref "U27") (pin "H9") (pinfunction "GND_H9") (pintype "power_in"))
      (node (ref "U27") (pin "J3") (pinfunction "GND_J3") (pintype "power_in"))
      (node (ref "U27") (pin "J4") (pinfunction "GND_J4") (pintype "power_in"))
      (node (ref "U27") (pin "J5") (pinfunction "GND_J5") (pintype "power_in"))
      (node (ref "U27") (pin "J6") (pinfunction "GND_J6") (pintype "power_in"))
      (node (ref "U27") (pin "J7") (pinfunction "GND_J7") (pintype "power_in"))
      (node (ref "U27") (pin "J8") (pinfunction "GND_J8") (pintype "power_in"))
      (node (ref "U27") (pin "J9") (pinfunction "GND_J9") (pintype "power_in"))
      (node (ref "U27") (pin "K3") (pinfunction "GND_K3") (pintype "power_in"))
      (node (ref "U27") (pin "K4") (pinfunction "GND_K4") (pintype "power_in"))
      (node (ref "U27") (pin "K5") (pinfunction "GND_K5") (pintype "power_in"))
      (node (ref "U27") (pin "K6") (pinfunction "GND_K6") (pintype "power_in"))
      (node (ref "U27") (pin "K7") (pinfunction "GND_K7") (pintype "power_in"))
      (node (ref "U27") (pin "K8") (pinfunction "GND_K8") (pintype "power_in"))
      (node (ref "U27") (pin "K9") (pinfunction "GND_K9") (pintype "power_in"))
      (node (ref "U27") (pin "L1") (pinfunction "GND_L1") (pintype "power_in"))
      (node (ref "U27") (pin "L5") (pinfunction "GND_L5") (pintype "power_in"))
      (node (ref "U27") (pin "L6") (pinfunction "GND_L6") (pintype "power_in"))
      (node (ref "U27") (pin "L7") (pinfunction "GND_L7") (pintype "power_in"))
      (node (ref "U27") (pin "L8") (pinfunction "GND_L8") (pintype "power_in"))
      (node (ref "U28") (pin "2") (pinfunction "GND_2") (pintype "power_in"))
      (node (ref "U29") (pin "3") (pinfunction "GND_3") (pintype "power_in"))
      (node (ref "U29") (pin "7") (pinfunction "EXPOSED_PAD_7") (pintype "power_in"))
      (node (ref "U3") (pin "3") (pinfunction "GND_3") (pintype "power_in"))
      (node (ref "U3") (pin "7") (pinfunction "EP_7") (pintype "bidirectional"))
      (node (ref "U31") (pin "5") (pinfunction "GND_5") (pintype "power_in"))
      (node (ref "U4") (pin "A1") (pinfunction "GND_A1") (pintype "power_in"))
      (node (ref "U4") (pin "A7") (pinfunction "GND_A7") (pintype "power_in"))
      (node (ref "U4") (pin "B2") (pinfunction "GND_B2") (pintype "power_in"))
      (node (ref "U4") (pin "B3") (pinfunction "GND_B3") (pintype "power_in"))
      (node (ref "U4") (pin "B4") (pinfunction "GND_B4") (pintype "power_in"))
      (node (ref "U4") (pin "B5") (pinfunction "GND_B5") (pintype "power_in"))
      (node (ref "U4") (pin "C2") (pinfunction "GND_C2") (pintype "power_in"))
      (node (ref "U4") (pin "C3") (pinfunction "GND_C3") (pintype "power_in"))
      (node (ref "U4") (pin "C4") (pinfunction "GND_C4") (pintype "power_in"))
      (node (ref "U4") (pin "C5") (pinfunction "GND_C5") (pintype "power_in"))
      (node (ref "U4") (pin "D2") (pinfunction "GND_D2") (pintype "power_in"))
      (node (ref "U4") (pin "D3") (pinfunction "GND_D3") (pintype "power_in"))
      (node (ref "U4") (pin "D4") (pinfunction "GND_D4") (pintype "power_in"))
      (node (ref "U4") (pin "D5") (pinfunction "GND_D5") (pintype "power_in"))
      (node (ref "U4") (pin "E1") (pinfunction "GND_E1") (pintype "power_in"))
      (node (ref "U4") (pin "E2") (pinfunction "GND_E2") (pintype "power_in"))
      (node (ref "U4") (pin "E3") (pinfunction "GND_E3") (pintype "power_in"))
      (node (ref "U4") (pin "E4") (pinfunction "GND_E4") (pintype "power_in"))
      (node (ref "U4") (pin "E5") (pinfunction "GND_E5") (pintype "power_in"))
      (node (ref "U4") (pin "E6") (pinfunction "GND_E6") (pintype "power_in"))
      (node (ref "U4") (pin "F3") (pinfunction "GND_F3") (pintype "power_in"))
      (node (ref "U4") (pin "F4") (pinfunction "GND_F4") (pintype "power_in"))
      (node (ref "U4") (pin "F5") (pinfunction "GND_F5") (pintype "power_in"))
      (node (ref "U4") (pin "G3") (pinfunction "GND_G3") (pintype "power_in"))
      (node (ref "U4") (pin "G4") (pinfunction "GND_G4") (pintype "power_in"))
      (node (ref "U4") (pin "G5") (pinfunction "GND_G5") (pintype "power_in"))
      (node (ref "U5") (pin "13") (pinfunction "AGND_13") (pintype "power_in"))
      (node (ref "U5") (pin "19") (pinfunction "PGND_19") (pintype "power_in"))
      (node (ref "U5") (pin "2") (pinfunction "SYNC/FREQ_2") (pintype "input"))
      (node (ref "U5") (pin "21") (pinfunction "EPAD_21") (pintype "power_in"))
      (node (ref "U5") (pin "4") (pinfunction "SLEW_4") (pintype "input"))
      (node (ref "U6") (pin "3") (pinfunction "GND_3") (pintype "power_in"))
      (node (ref "U6") (pin "7") (pinfunction "EXPOSED_PAD_7") (pintype "power_in"))
      (node (ref "U7") (pin "5") (pinfunction "GND_5") (pintype "power_in"))
    )
    (net (code "25") (name "Net-(C13-Pad2)") (class "Default")
      (node (ref "C13") (pin "2") (pinfunction "2_2") (pintype "passive"))
      (node (ref "R13") (pin "1") (pinfunction "1_1") (pintype "passive"))
    )
    (net (code "26") (name "Net-(C18-Pad2)") (class "Default")
      (node (ref "C18") (pin "2") (pinfunction "2_2") (pintype "passive"))
      (node (ref "R16") (pin "1") (pinfunction "1_1") (pintype "passive"))
    )
    (net (code "27") (name "Net-(C50-Pad2)") (class "Default")
      (node (ref "C50") (pin "2") (pinfunction "2_2") (pintype "passive"))
      (node (ref "R38") (pin "1") (pinfunction "1_1") (pintype "passive"))
    )
    (net (code "28") (name "Net-(C97-Pad2)") (class "Default")
      (node (ref "C97") (pin "2") (pinfunction "2_2") (pintype "passive"))
      (node (ref "R66") (pin "1") (pinfunction "1_1") (pintype "passive"))
    )
    (net (code "29") (name "Net-(D1-A)") (class "Default")
      (node (ref "D1") (pin "2") (pinfunction "A_2") (pintype "passive"))
      (node (ref "L2") (pin "2") (pinfunction "2_2") (pintype "passive"))
      (node (ref "U5") (pin "20") (pinfunction "SW1_20") (pintype "passive"))
    )
    (net (code "30") (name "Net-(D2-C)") (class "Default")
      (node (ref "D2") (pin "1") (pinfunction "C_1") (pintype "passive"))
      (node (ref "L1") (pin "1") (pinfunction "1_1") (pintype "passive"))
      (node (ref "U5") (pin "18") (pinfunction "SW2_18") (pintype "passive"))
    )
    (net (code "31") (name "Net-(R53-Pad2)") (class "Default")
      (node (ref "R53") (pin "2") (pinfunction "2_2") (pintype "passive"))
      (node (ref "U27") (pin "F10") (pinfunction "SVIN_F10") (pintype "input"))
      (node (ref "U27") (pin "F11") (pinfunction "SVIN_F11") (pintype "input"))
      (node (ref "U27") (pin "G10") (pinfunction "VIN_G10") (pintype "input"))
      (node (ref "U27") (pin "G11") (pinfunction "VIN_G11") (pintype "input"))
      (node (ref "U27") (pin "H10") (pinfunction "VIN_H10") (pintype "input"))
      (node (ref "U27") (pin "H11") (pinfunction "VIN_H11") (pintype "input"))
      (node (ref "U27") (pin "J10") (pinfunction "VIN_J10") (pintype "input"))
      (node (ref "U27") (pin "J11") (pinfunction "VIN_J11") (pintype "input"))
      (node (ref "U27") (pin "K10") (pinfunction "VIN_K10") (pintype "input"))
      (node (ref "U27") (pin "K11") (pinfunction "VIN_K11") (pintype "input"))
      (node (ref "U27") (pin "L10") (pinfunction "VIN_L10") (pintype "input"))
      (node (ref "U27") (pin "L11") (pinfunction "VIN_L11") (pintype "input"))
    )
    (net (code "32") (name "Net-(R55-Pad1)") (class "Default")
      (node (ref "R55") (pin "1") (pinfunction "1_1") (pintype "passive"))
      (node (ref "U27") (pin "A1") (pinfunction "VOUT_A1") (pintype "output"))
      (node (ref "U27") (pin "A2") (pinfunction "VOUT_A2") (pintype "output"))
      (node (ref "U27") (pin "A3") (pinfunction "VOUT_A3") (pintype "output"))
      (node (ref "U27") (pin "A4") (pinfunction "VOUT_A4") (pintype "output"))
      (node (ref "U27") (pin "A5") (pinfunction "VOUT_A5") (pintype "output"))
      (node (ref "U27") (pin "A6") (pinfunction "VOUT_A6") (pintype "output"))
      (node (ref "U27") (pin "B1") (pinfunction "VOUT_B1") (pintype "output"))
      (node (ref "U27") (pin "B2") (pinfunction "VOUT_B2") (pintype "output"))
      (node (ref "U27") (pin "B3") (pinfunction "VOUT_B3") (pintype "output"))
      (node (ref "U27") (pin "B4") (pinfunction "VOUT_B4") (pintype "output"))
      (node (ref "U27") (pin "B5") (pinfunction "VOUT_B5") (pintype "output"))
      (node (ref "U27") (pin "B6") (pinfunction "VOUT_B6") (pintype "output"))
      (node (ref "U27") (pin "C1") (pinfunction "VOUT_C1") (pintype "output"))
      (node (ref "U27") (pin "C2") (pinfunction "VOUT_C2") (pintype "output"))
      (node (ref "U27") (pin "C3") (pinfunction "VOUT_C3") (pintype "output"))
      (node (ref "U27") (pin "C4") (pinfunction "VOUT_C4") (pintype "output"))
      (node (ref "U27") (pin "C5") (pinfunction "VOUT_C5") (pintype "output"))
      (node (ref "U27") (pin "C6") (pinfunction "VOUT_C6") (pintype "output"))
    )
    (net (code "33") (name "Net-(U3-FB{slash}NC)") (class "Default")
      (node (ref "R7") (pin "1") (pinfunction "1_1") (pintype "passive"))
      (node (ref "R8") (pin "2") (pinfunction "2_2") (pintype "passive"))
      (node (ref "U3") (pin "2") (pinfunction "FB/NC_2") (pintype "bidirectional"))
    )
    (net (code "34") (name "Net-(U4-FB1)") (class "Default")
      (node (ref "R10") (pin "2") (pinfunction "2_2") (pintype "passive"))
      (node (ref "U4") (pin "D7") (pinfunction "FB1_D7") (pintype "passive"))
    )
    (net (code "35") (name "Net-(U4-FB2)") (class "Default")
      (node (ref "R11") (pin "2") (pinfunction "2_2") (pintype "passive"))
      (node (ref "U4") (pin "C7") (pinfunction "FB2_C7") (pintype "passive"))
    )
    (net (code "36") (name "Net-(U4-OM)") (class "Default")
      (node (ref "U4") (pin "C6") (pinfunction "OM_C6") (pintype "passive"))
      (node (ref "U4") (pin "D6") (pinfunction "OMC_D6") (pintype "passive"))
    )
    (net (code "37") (name "Net-(U4-RT)") (class "Default")
      (node (ref "R9") (pin "2") (pinfunction "2_2") (pintype "passive"))
      (node (ref "U4") (pin "B7") (pinfunction "RT_B7") (pintype "passive"))
    )
    (net (code "38") (name "Net-(U4-TRSS1)") (class "Default")
      (node (ref "C77") (pin "2") (pinfunction "2_2") (pintype "passive"))
      (node (ref "U4") (pin "B6") (pinfunction "TRSS1_B6") (pintype "passive"))
    )
    (net (code "39") (name "Net-(U4-TRSS2)") (class "Default")
      (node (ref "C78") (pin "2") (pinfunction "2_2") (pintype "passive"))
      (node (ref "U4") (pin "A6") (pinfunction "TRSS2_A6") (pintype "passive"))
    )
    (net (code "40") (name "Net-(U5-COMP1)") (class "Default")
      (node (ref "R13") (pin "2") (pinfunction "2_2") (pintype "passive"))
      (node (ref "U5") (pin "6") (pinfunction "COMP1_6") (pintype "passive"))
    )
    (net (code "41") (name "Net-(U5-COMP2)") (class "Default")
      (node (ref "R16") (pin "2") (pinfunction "2_2") (pintype "passive"))
      (node (ref "U5") (pin "10") (pinfunction "COMP2_10") (pintype "passive"))
    )
    (net (code "42") (name "Net-(U5-FB1)") (class "Default")
      (node (ref "R12") (pin "2") (pinfunction "2_2") (pintype "passive"))
      (node (ref "R22") (pin "2") (pinfunction "2_2") (pintype "passive"))
      (node (ref "U5") (pin "5") (pinfunction "FB1_5") (pintype "passive"))
    )
    (net (code "43") (name "Net-(U5-FB2)") (class "Default")
      (node (ref "C98") (pin "2") (pinfunction "2_2") (pintype "passive"))
      (node (ref "R15") (pin "2") (pinfunction "2_2") (pintype "passive"))
      (node (ref "R23") (pin "2") (pinfunction "2_2") (pintype "passive"))
      (node (ref "U5") (pin "11") (pinfunction "FB2_11") (pintype "passive"))
    )
    (net (code "44") (name "Net-(U5-INBK)") (class "Default")
      (node (ref "L2") (pin "1") (pinfunction "1_1") (pintype "passive"))
      (node (ref "U5") (pin "1") (pinfunction "INBK_1") (pintype "passive"))
    )
    (net (code "45") (name "Net-(U5-PVIN1)") (class "Default")
      (node (ref "C14") (pin "2") (pinfunction "2_2") (pintype "passive"))
      (node (ref "FB4") (pin "2") (pinfunction "2_2") (pintype "passive"))
      (node (ref "U5") (pin "15") (pinfunction "PVIN1_15") (pintype "power_in"))
      (node (ref "U5") (pin "16") (pinfunction "PVINSYS_16") (pintype "power_in"))
      (node (ref "U5") (pin "17") (pinfunction "PVIN2_17") (pintype "power_in"))
    )
    (net (code "46") (name "Net-(U5-SS)") (class "Default")
      (node (ref "R14") (pin "2") (pinfunction "2_2") (pintype "passive"))
      (node (ref "U5") (pin "8") (pinfunction "SS_8") (pintype "passive"))
    )
    (net (code "47") (name "Net-(U5-VREF)") (class "Default")
      (node (ref "R15") (pin "1") (pinfunction "1_1") (pintype "passive"))
      (node (ref "U5") (pin "12") (pinfunction "VREF_12") (pintype "passive"))
    )
    (net (code "48") (name "Net-(U6-SENSE{slash}ADJ)") (class "Default")
      (node (ref "R17") (pin "1") (pinfunction "1_1") (pintype "passive"))
      (node (ref "R21") (pin "2") (pinfunction "2_2") (pintype "passive"))
      (node (ref "U6") (pin "2") (pinfunction "SENSE/ADJ_2") (pintype "passive"))
    )
    (net (code "49") (name "Net-(U6-SS)") (class "Default")
      (node (ref "C47") (pin "1") (pinfunction "1_1") (pintype "passive"))
      (node (ref "U6") (pin "5") (pinfunction "SS_5") (pintype "passive"))
    )
    (net (code "50") (name "Net-(U7-ADJ)") (class "Default")
      (node (ref "R37") (pin "2") (pinfunction "2_2") (pintype "passive"))
      (node (ref "R38") (pin "2") (pinfunction "2_2") (pintype "passive"))
      (node (ref "R39") (pin "2") (pinfunction "2_2") (pintype "passive"))
      (node (ref "U7") (pin "2") (pinfunction "ADJ_2") (pintype "input"))
    )
    (net (code "51") (name "Net-(U26-FS0)") (class "Default")
      (node (ref "R18") (pin "2") (pinfunction "2_2") (pintype "passive"))
      (node (ref "U26") (pin "7") (pinfunction "FS0_7") (pintype "input"))
    )
    (net (code "52") (name "Net-(U26-FS1)") (class "Default")
      (node (ref "R19") (pin "2") (pinfunction "2_2") (pintype "passive"))
      (node (ref "U26") (pin "6") (pinfunction "FS1_6") (pintype "input"))
    )
    (net (code "53") (name "Net-(U27A-IIN)") (class "Default")
      (node (ref "C66") (pin "2") (pinfunction "2_2") (pintype "passive"))
      (node (ref "C67") (pin "2") (pinfunction "2_2") (pintype "passive"))
      (node (ref "C68") (pin "2") (pinfunction "2_2") (pintype "passive"))
      (node (ref "FB11") (pin "2") (pinfunction "2_2") (pintype "passive"))
      (node (ref "R53") (pin "1") (pinfunction "1_1") (pintype "passive"))
      (node (ref "U27") (pin "L9") (pinfunction "IIN_L9") (pintype "input"))
    )
    (net (code "54") (name "Net-(U27A-IOUT)") (class "Default")
      (node (ref "C69") (pin "2") (pinfunction "2_2") (pintype "passive"))
      (node (ref "C71") (pin "2") (pinfunction "2_2") (pintype "passive"))
      (node (ref "FB12") (pin "1") (pinfunction "1_1") (pintype "passive"))
      (node (ref "R55") (pin "2") (pinfunction "2_2") (pintype "passive"))
      (node (ref "R56") (pin "2") (pinfunction "2_2") (pintype "passive"))
      (node (ref "U27") (pin "D1") (pinfunction "IOUT_D1") (pintype "output"))
    )
    (net (code "55") (name "Net-(U27A-RT)") (class "Default")
      (node (ref "R60") (pin "2") (pinfunction "2_2") (pintype "passive"))
      (node (ref "U27") (pin "H1") (pinfunction "RT_H1") (pintype "passive"))
    )
    (net (code "56") (name "Net-(U27A-SS)") (class "Default")
      (node (ref "C75") (pin "2") (pinfunction "2_2") (pintype "passive"))
      (node (ref "U27") (pin "K1") (pinfunction "SS_K1") (pintype "passive"))
    )
    (net (code "57") (name "Net-(U29-SENSE{slash}ADJ)") (class "Default")
      (node (ref "R52") (pin "2") (pinfunction "2_2") (pintype "passive"))
      (node (ref "R62") (pin "2") (pinfunction "2_2") (pintype "passive"))
      (node (ref "U29") (pin "2") (pinfunction "SENSE/ADJ_2") (pintype "passive"))
    )
    (net (code "58") (name "Net-(U29-SS)") (class "Default")
      (node (ref "C94") (pin "1") (pinfunction "1_1") (pintype "passive"))
      (node (ref "U29") (pin "5") (pinfunction "SS_5") (pintype "passive"))
    )
    (net (code "59") (name "Net-(U31-ADJ)") (class "Default")
      (node (ref "R63") (pin "2") (pinfunction "2_2") (pintype "passive"))
      (node (ref "R66") (pin "2") (pinfunction "2_2") (pintype "passive"))
      (node (ref "R77") (pin "2") (pinfunction "2_2") (pintype "passive"))
      (node (ref "U31") (pin "2") (pinfunction "ADJ_2") (pintype "input"))
    )
    (net (code "60") (name "V_DUT") (class "Default")
      (node (ref "C70") (pin "2") (pinfunction "2_2") (pintype "passive"))
      (node (ref "FB12") (pin "2") (pinfunction "2_2") (pintype "passive"))
    )
    (net (code "61") (name "unconnected-(U4-CLKOUT-PadD1)") (class "Default")
      (node (ref "U4") (pin "D1") (pinfunction "CLKOUT_D1") (pintype "output+no_connect"))
    )
    (net (code "62") (name "unconnected-(U4-PG1-PadB1)") (class "Default")
      (node (ref "U4") (pin "B1") (pinfunction "PG1_B1") (pintype "open_collector+no_connect"))
    )
    (net (code "63") (name "unconnected-(U4-PG2-PadA2)") (class "Default")
      (node (ref "U4") (pin "A2") (pinfunction "PG2_A2") (pintype "open_collector+no_connect"))
    )
    (net (code "64") (name "unconnected-(U4-SYNC-PadC1)") (class "Default")
      (node (ref "U4") (pin "C1") (pinfunction "SYNC_C1") (pintype "passive+no_connect"))
    )
    (net (code "65") (name "unconnected-(U7-NC-Pad4)") (class "Default")
      (node (ref "U7") (pin "4") (pinfunction "NC_4") (pintype "passive+no_connect"))
    )
    (net (code "66") (name "unconnected-(U26-FS2-Pad5)") (class "Default")
      (node (ref "U26") (pin "5") (pinfunction "FS2_5") (pintype "input+no_connect"))
    )
    (net (code "67") (name "unconnected-(U26-FS3-Pad4)") (class "Default")
      (node (ref "U26") (pin "4") (pinfunction "FS3_4") (pintype "input+no_connect"))
    )
    (net (code "68") (name "unconnected-(U26-OUT2-Pad12)") (class "Default")
      (node (ref "U26") (pin "12") (pinfunction "OUT2_12") (pintype "output+no_connect"))
    )
    (net (code "69") (name "unconnected-(U26-OUT3-Pad14)") (class "Default")
      (node (ref "U26") (pin "14") (pinfunction "OUT3_14") (pintype "output+no_connect"))
    )
    (net (code "70") (name "unconnected-(U27A-CLKOUT-PadG1)") (class "Default")
      (node (ref "U27") (pin "G1") (pinfunction "CLKOUT_G1") (pintype "output+no_connect"))
    )
    (net (code "71") (name "unconnected-(U27A-COMP-PadJ2)") (class "Default")
      (node (ref "U27") (pin "J2") (pinfunction "COMP_J2") (pintype "passive+no_connect"))
    )
    (net (code "72") (name "unconnected-(U27A-LL-PadF1)") (class "Default")
      (node (ref "U27") (pin "F1") (pinfunction "LL_F1") (pintype "passive+no_connect"))
    )
    (net (code "73") (name "unconnected-(U27A-MODE-PadG2)") (class "Default")
      (node (ref "U27") (pin "G2") (pinfunction "MODE_G2") (pintype "passive+no_connect"))
    )
    (net (code "74") (name "unconnected-(U31-NC-Pad4)") (class "Default")
      (node (ref "U31") (pin "4") (pinfunction "NC_4") (pintype "passive+no_connect"))
    )
  )
)
